# Chov2_main.net
KiCad netlist of a schematic drawn in Altium Designer
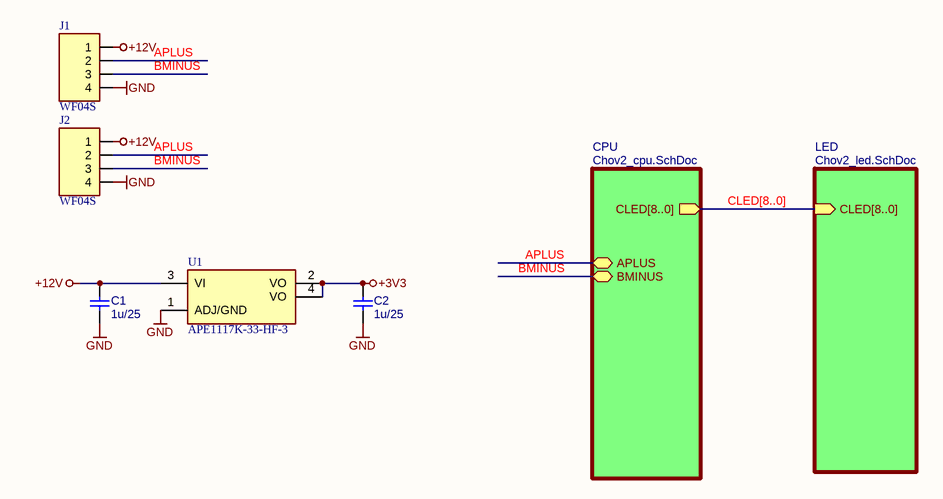
[diagram p0: Chov2_main.SchDoc]

(export (version "E")
  (design (tool "Eeschema 10.0.6"))
  (components
    (comp (ref "C1")
      (value "CL21B105KAFNNNG")
      (footprint "0805")
      (fields (field (name "OTHERPARAMS") "1u/25") (field (name "TOLERANCE") "10%"))
      (libsource (lib "Parts") (part "C"))
    )
    (comp (ref "C2")
      (value "CL21B105KAFNNNG")
      (footprint "0805")
      (fields (field (name "OTHERPARAMS") "1u/25") (field (name "TOLERANCE") "10%"))
      (libsource (lib "Parts") (part "C"))
    )
    (comp (ref "J1") (value "WF04S") (footprint "WF04S") (libsource (lib "Parts") (part "HEADER4")))
    (comp (ref "J2") (value "WF04S") (footprint "WF04S") (libsource (lib "Parts") (part "HEADER4")))
    (comp (ref "U1")
      (value "APE1117K-33-HF-3")
      (footprint "SOT-223")
      (libsource (lib "Parts") (part "LM1117IMP"))
    )
  )
  (nets
    (net (code "10") (name "+3V3") (class "Default")
      (node (ref "C2") (pin "1") (pinfunction "1_1") (pintype "passive"))
      (node (ref "U1") (pin "2") (pinfunction "VO_2") (pintype "passive"))
      (node (ref "U1") (pin "4") (pinfunction "VO_4") (pintype "passive"))
    )
    (net (code "11") (name "+12V") (class "Default")
      (node (ref "C1") (pin "1") (pinfunction "1_1") (pintype "passive"))
      (node (ref "J1") (pin "1") (pinfunction "1_1") (pintype "passive"))
      (node (ref "J2") (pin "1") (pinfunction "1_1") (pintype "passive"))
      (node (ref "U1") (pin "3") (pinfunction "VI_3") (pintype "passive"))
    )
    (net (code "12") (name "/APLUS") (class "Default")
      (node (ref "J1") (pin "2") (pinfunction "2_2") (pintype "passive"))
      (node (ref "J2") (pin "2") (pinfunction "2_2") (pintype "passive"))
    )
    (net (code "13") (name "/BMINUS") (class "Default")
      (node (ref "J1") (pin "3") (pinfunction "3_3") (pintype "passive"))
      (node (ref "J2") (pin "3") (pinfunction "3_3") (pintype "passive"))
    )
    (net (code "15") (name "GND") (class "Default")
      (node (ref "C1") (pin "2") (pinfunction "2_2") (pintype "passive"))
      (node (ref "C2") (pin "2") (pinfunction "2_2") (pintype "passive"))
      (node (ref "J1") (pin "4") (pinfunction "4_4") (pintype "passive"))
      (node (ref "J2") (pin "4") (pinfunction "4_4") (pintype "passive"))
      (node (ref "U1") (pin "1") (pinfunction "ADJ/GND_1") (pintype "passive"))
    )
  )
)
